# RelayBoard1_0.net
KiCad netlist of a schematic drawn in EAGLE
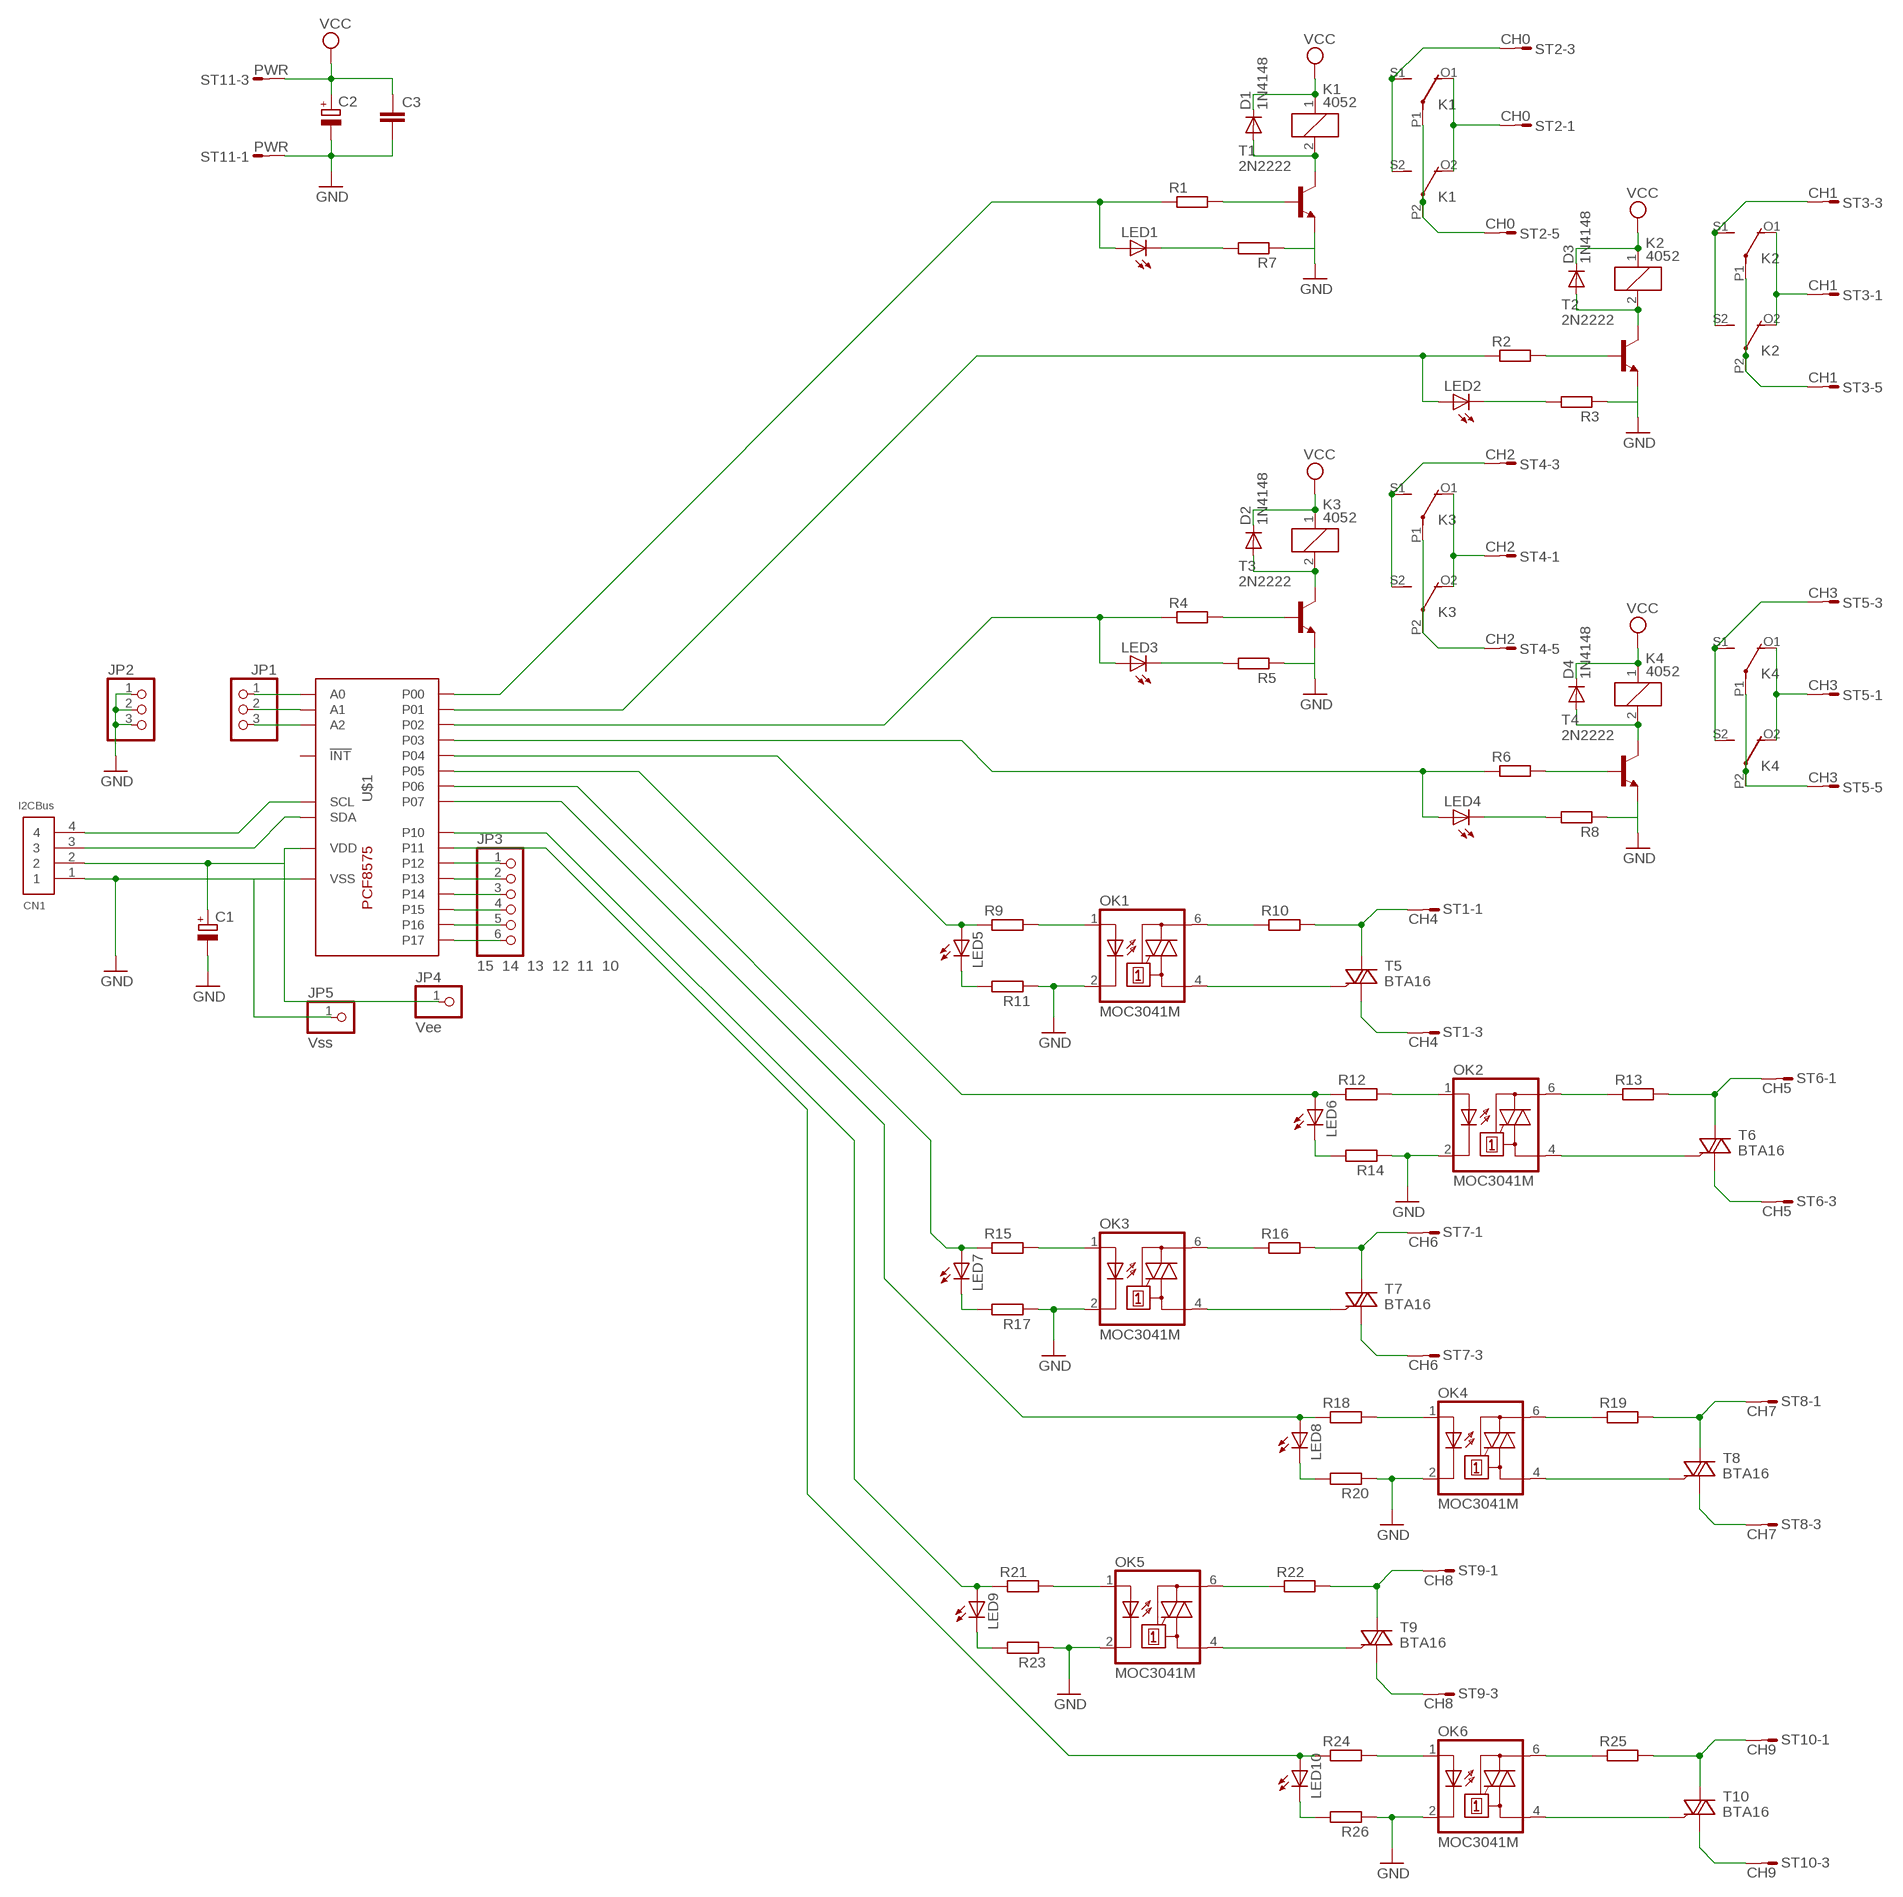
[diagram p0: schematic, sheet 1]

(export (version "E")
  (design (tool "Eeschema 10.0.6"))
  (components
    (comp (ref "C1")
      (value "CPOL-EUE3.5-8")
      (footprint "eagle-import:E3,5-8")
      (libsource (lib "eagle-import") (part "resistor_CPOL-EUE3.5-8"))
    )
    (comp (ref "C2")
      (value "CPOL-EUE2.5-7")
      (footprint "eagle-import:E2,5-7")
      (libsource (lib "eagle-import") (part "CPOL-EUE2.5-7"))
    )
    (comp (ref "C3")
      (value "C-EU050-025X075")
      (footprint "eagle-import:C050-025X075")
      (libsource (lib "eagle-import") (part "C-EU050-025X075"))
    )
    (comp (ref "CN1")
      (value "I2CBus")
      (footprint "eagle-import:1X04-BIG")
      (libsource (lib "eagle-import") (part "1X4-BIG"))
    )
    (comp (ref "D1")
      (value "1N4148")
      (footprint "eagle-import:DO35-7")
      (libsource (lib "eagle-import") (part "1N4148DO35-7"))
    )
    (comp (ref "D2")
      (value "1N4148")
      (footprint "eagle-import:DO35-7")
      (libsource (lib "eagle-import") (part "1N4148DO35-7"))
    )
    (comp (ref "D3")
      (value "1N4148")
      (footprint "eagle-import:DO35-7")
      (libsource (lib "eagle-import") (part "1N4148DO35-7"))
    )
    (comp (ref "D4")
      (value "1N4148")
      (footprint "eagle-import:DO35-7")
      (libsource (lib "eagle-import") (part "1N4148DO35-7"))
    )
    (comp (ref "JP1")
      (value "PINHD-1X3")
      (footprint "eagle-import:1X03")
      (libsource (lib "eagle-import") (part "PINHD-1X3"))
    )
    (comp (ref "JP2")
      (value "PINHD-1X3")
      (footprint "eagle-import:1X03")
      (libsource (lib "eagle-import") (part "PINHD-1X3"))
    )
    (comp (ref "JP3")
      (value "15 14 13 12 11 10")
      (footprint "eagle-import:1X06-CLEANBIG")
      (libsource (lib "eagle-import") (part "PINHD-1X6CB"))
    )
    (comp (ref "JP4")
      (value "Vee")
      (footprint "eagle-import:1X01-CLEANBIG")
      (libsource (lib "eagle-import") (part "PINHD-1X1CB"))
    )
    (comp (ref "JP5")
      (value "Vss")
      (footprint "eagle-import:1X01-CLEANBIG")
      (libsource (lib "eagle-import") (part "PINHD-1X1CB"))
    )
    (comp (ref "K1")
      (value "4052")
      (footprint "eagle-import:F4052")
      (libsource (lib "eagle-import") (part "4052"))
    )
    (comp (ref "K2")
      (value "4052")
      (footprint "eagle-import:F4052")
      (libsource (lib "eagle-import") (part "4052"))
    )
    (comp (ref "K3")
      (value "4052")
      (footprint "eagle-import:F4052")
      (libsource (lib "eagle-import") (part "4052"))
    )
    (comp (ref "K4")
      (value "4052")
      (footprint "eagle-import:F4052")
      (libsource (lib "eagle-import") (part "4052"))
    )
    (comp (ref "LED1")
      (value "LED3MM")
      (footprint "eagle-import:LED3MM")
      (libsource (lib "eagle-import") (part "LED3MM"))
    )
    (comp (ref "LED2")
      (value "LED3MM")
      (footprint "eagle-import:LED3MM")
      (libsource (lib "eagle-import") (part "LED3MM"))
    )
    (comp (ref "LED3")
      (value "LED3MM")
      (footprint "eagle-import:LED3MM")
      (libsource (lib "eagle-import") (part "LED3MM"))
    )
    (comp (ref "LED4")
      (value "LED3MM")
      (footprint "eagle-import:LED3MM")
      (libsource (lib "eagle-import") (part "LED3MM"))
    )
    (comp (ref "LED5")
      (value "LEDCHIPLED_0805")
      (footprint "eagle-import:CHIPLED_0805")
      (libsource (lib "eagle-import") (part "LEDCHIPLED_0805"))
    )
    (comp (ref "LED6")
      (value "LEDCHIPLED_0805")
      (footprint "eagle-import:CHIPLED_0805")
      (libsource (lib "eagle-import") (part "LEDCHIPLED_0805"))
    )
    (comp (ref "LED7")
      (value "LEDCHIPLED_0805")
      (footprint "eagle-import:CHIPLED_0805")
      (libsource (lib "eagle-import") (part "LEDCHIPLED_0805"))
    )
    (comp (ref "LED8")
      (value "LEDCHIPLED_0805")
      (footprint "eagle-import:CHIPLED_0805")
      (libsource (lib "eagle-import") (part "LEDCHIPLED_0805"))
    )
    (comp (ref "LED9")
      (value "LEDCHIPLED_0805")
      (footprint "eagle-import:CHIPLED_0805")
      (libsource (lib "eagle-import") (part "LEDCHIPLED_0805"))
    )
    (comp (ref "LED10")
      (value "LEDCHIPLED_0805")
      (footprint "eagle-import:CHIPLED_0805")
      (libsource (lib "eagle-import") (part "LEDCHIPLED_0805"))
    )
    (comp (ref "OK1")
      (value "MOC3041M")
      (footprint "eagle-import:DIL06")
      (fields (field (name "MF") "FAIRCHILD SEMICONDUCTOR"))
      (libsource (lib "eagle-import") (part "MOC3041M"))
    )
    (comp (ref "OK2")
      (value "MOC3041M")
      (footprint "eagle-import:DIL06")
      (fields (field (name "MF") "FAIRCHILD SEMICONDUCTOR"))
      (libsource (lib "eagle-import") (part "MOC3041M"))
    )
    (comp (ref "OK3")
      (value "MOC3041M")
      (footprint "eagle-import:DIL06")
      (fields (field (name "MF") "FAIRCHILD SEMICONDUCTOR"))
      (libsource (lib "eagle-import") (part "MOC3041M"))
    )
    (comp (ref "OK4")
      (value "MOC3041M")
      (footprint "eagle-import:DIL06")
      (fields (field (name "MF") "FAIRCHILD SEMICONDUCTOR"))
      (libsource (lib "eagle-import") (part "MOC3041M"))
    )
    (comp (ref "OK5")
      (value "MOC3041M")
      (footprint "eagle-import:DIL06")
      (fields (field (name "MF") "FAIRCHILD SEMICONDUCTOR"))
      (libsource (lib "eagle-import") (part "MOC3041M"))
    )
    (comp (ref "OK6")
      (value "MOC3041M")
      (footprint "eagle-import:DIL06")
      (fields (field (name "MF") "FAIRCHILD SEMICONDUCTOR"))
      (libsource (lib "eagle-import") (part "MOC3041M"))
    )
    (comp (ref "R1")
      (value "R-EU_0204/7")
      (footprint "eagle-import:0204_7")
      (libsource (lib "eagle-import") (part "R-EU_0204/7"))
    )
    (comp (ref "R2")
      (value "R-EU_0204/7")
      (footprint "eagle-import:0204_7")
      (libsource (lib "eagle-import") (part "R-EU_0204/7"))
    )
    (comp (ref "R3")
      (value "R-EU_0207/2V")
      (footprint "eagle-import:0207_2V")
      (libsource (lib "eagle-import") (part "R-EU_0207/2V"))
    )
    (comp (ref "R4")
      (value "R-EU_0204/7")
      (footprint "eagle-import:0204_7")
      (libsource (lib "eagle-import") (part "R-EU_0204/7"))
    )
    (comp (ref "R5")
      (value "R-EU_0207/2V")
      (footprint "eagle-import:0207_2V")
      (libsource (lib "eagle-import") (part "R-EU_0207/2V"))
    )
    (comp (ref "R6")
      (value "R-EU_0204/7")
      (footprint "eagle-import:0204_7")
      (libsource (lib "eagle-import") (part "R-EU_0204/7"))
    )
    (comp (ref "R7")
      (value "R-EU_0207/2V")
      (footprint "eagle-import:0207_2V")
      (libsource (lib "eagle-import") (part "R-EU_0207/2V"))
    )
    (comp (ref "R8")
      (value "R-EU_0207/2V")
      (footprint "eagle-import:0207_2V")
      (libsource (lib "eagle-import") (part "R-EU_0207/2V"))
    )
    (comp (ref "R9")
      (value "R-EU_0207/2V")
      (footprint "eagle-import:0207_2V")
      (libsource (lib "eagle-import") (part "R-EU_0207/2V"))
    )
    (comp (ref "R10")
      (value "R-EU_0207/7")
      (footprint "eagle-import:0207_7")
      (libsource (lib "eagle-import") (part "R-EU_0207/7"))
    )
    (comp (ref "R11")
      (value "R-EU_M0805")
      (footprint "eagle-import:M0805")
      (libsource (lib "eagle-import") (part "R-EU_M0805"))
    )
    (comp (ref "R12")
      (value "R-EU_0207/2V")
      (footprint "eagle-import:0207_2V")
      (libsource (lib "eagle-import") (part "R-EU_0207/2V"))
    )
    (comp (ref "R13")
      (value "R-EU_0207/7")
      (footprint "eagle-import:0207_7")
      (libsource (lib "eagle-import") (part "R-EU_0207/7"))
    )
    (comp (ref "R14")
      (value "R-EU_M0805")
      (footprint "eagle-import:M0805")
      (libsource (lib "eagle-import") (part "R-EU_M0805"))
    )
    (comp (ref "R15")
      (value "R-EU_0207/2V")
      (footprint "eagle-import:0207_2V")
      (libsource (lib "eagle-import") (part "R-EU_0207/2V"))
    )
    (comp (ref "R16")
      (value "R-EU_0207/7")
      (footprint "eagle-import:0207_7")
      (libsource (lib "eagle-import") (part "R-EU_0207/7"))
    )
    (comp (ref "R17")
      (value "R-EU_M0805")
      (footprint "eagle-import:M0805")
      (libsource (lib "eagle-import") (part "R-EU_M0805"))
    )
    (comp (ref "R18")
      (value "R-EU_0207/2V")
      (footprint "eagle-import:0207_2V")
      (libsource (lib "eagle-import") (part "R-EU_0207/2V"))
    )
    (comp (ref "R19")
      (value "R-EU_0207/7")
      (footprint "eagle-import:0207_7")
      (libsource (lib "eagle-import") (part "R-EU_0207/7"))
    )
    (comp (ref "R20")
      (value "R-EU_M0805")
      (footprint "eagle-import:M0805")
      (libsource (lib "eagle-import") (part "R-EU_M0805"))
    )
    (comp (ref "R21")
      (value "R-EU_0207/2V")
      (footprint "eagle-import:0207_2V")
      (libsource (lib "eagle-import") (part "R-EU_0207/2V"))
    )
    (comp (ref "R22")
      (value "R-EU_0207/7")
      (footprint "eagle-import:0207_7")
      (libsource (lib "eagle-import") (part "R-EU_0207/7"))
    )
    (comp (ref "R23")
      (value "R-EU_M0805")
      (footprint "eagle-import:M0805")
      (libsource (lib "eagle-import") (part "R-EU_M0805"))
    )
    (comp (ref "R24")
      (value "R-EU_0207/2V")
      (footprint "eagle-import:0207_2V")
      (libsource (lib "eagle-import") (part "R-EU_0207/2V"))
    )
    (comp (ref "R25")
      (value "R-EU_0207/7")
      (footprint "eagle-import:0207_7")
      (libsource (lib "eagle-import") (part "R-EU_0207/7"))
    )
    (comp (ref "R26")
      (value "R-EU_M0805")
      (footprint "eagle-import:M0805")
      (libsource (lib "eagle-import") (part "R-EU_M0805"))
    )
    (comp (ref "ST1")
      (value "CH4")
      (footprint "eagle-import:MSF3")
      (libsource (lib "eagle-import") (part "MSF3"))
    )
    (comp (ref "ST2")
      (value "CH0")
      (footprint "eagle-import:MSF5")
      (libsource (lib "eagle-import") (part "MSF5"))
    )
    (comp (ref "ST3")
      (value "CH1")
      (footprint "eagle-import:MSF5")
      (libsource (lib "eagle-import") (part "MSF5"))
    )
    (comp (ref "ST4")
      (value "CH2")
      (footprint "eagle-import:MSF5")
      (libsource (lib "eagle-import") (part "MSF5"))
    )
    (comp (ref "ST5")
      (value "CH3")
      (footprint "eagle-import:MSF5")
      (libsource (lib "eagle-import") (part "MSF5"))
    )
    (comp (ref "ST6")
      (value "CH5")
      (footprint "eagle-import:MSF3")
      (libsource (lib "eagle-import") (part "MSF3"))
    )
    (comp (ref "ST7")
      (value "CH6")
      (footprint "eagle-import:MSF3")
      (libsource (lib "eagle-import") (part "MSF3"))
    )
    (comp (ref "ST8")
      (value "CH7")
      (footprint "eagle-import:MSF3")
      (libsource (lib "eagle-import") (part "MSF3"))
    )
    (comp (ref "ST9")
      (value "CH8")
      (footprint "eagle-import:MSF3")
      (libsource (lib "eagle-import") (part "MSF3"))
    )
    (comp (ref "ST10")
      (value "CH9")
      (footprint "eagle-import:MSF3")
      (libsource (lib "eagle-import") (part "MSF3"))
    )
    (comp (ref "ST11")
      (value "PWR")
      (footprint "eagle-import:MSF3")
      (libsource (lib "eagle-import") (part "MSF3"))
    )
    (comp (ref "T1")
      (value "2N2222")
      (footprint "eagle-import:TO92-EBC-OVAL")
      (libsource (lib "eagle-import") (part "2N2222"))
    )
    (comp (ref "T2")
      (value "2N2222")
      (footprint "eagle-import:TO92-EBC-OVAL")
      (libsource (lib "eagle-import") (part "2N2222"))
    )
    (comp (ref "T3")
      (value "2N2222")
      (footprint "eagle-import:TO92-EBC-OVAL")
      (libsource (lib "eagle-import") (part "2N2222"))
    )
    (comp (ref "T4")
      (value "2N2222")
      (footprint "eagle-import:TO92-EBC-OVAL")
      (libsource (lib "eagle-import") (part "2N2222"))
    )
    (comp (ref "T5")
      (value "BTA16")
      (footprint "eagle-import:TO220BV")
      (libsource (lib "eagle-import") (part "BT138-V"))
    )
    (comp (ref "T6")
      (value "BTA16")
      (footprint "eagle-import:TO220BV")
      (libsource (lib "eagle-import") (part "BT138-V"))
    )
    (comp (ref "T7")
      (value "BTA16")
      (footprint "eagle-import:TO220BV")
      (libsource (lib "eagle-import") (part "BT138-V"))
    )
    (comp (ref "T8")
      (value "BTA16")
      (footprint "eagle-import:TO220BV")
      (libsource (lib "eagle-import") (part "BT138-V"))
    )
    (comp (ref "T9")
      (value "BTA16")
      (footprint "eagle-import:TO220BV")
      (libsource (lib "eagle-import") (part "BT138-V"))
    )
    (comp (ref "T10")
      (value "BTA16")
      (footprint "eagle-import:TO220BV")
      (libsource (lib "eagle-import") (part "BT138-V"))
    )
    (comp (ref "U$1")
      (value "PCF8575C")
      (footprint "eagle-import:SOP24")
      (libsource (lib "eagle-import") (part "PCF8575C"))
    )
  )
  (nets
    (net (code "1") (name "GND") (class "Default")
      (node (ref "C1") (pin "-") (pinfunction "-_-") (pintype "passive"))
      (node (ref "C2") (pin "-") (pinfunction "-_-") (pintype "passive"))
      (node (ref "C3") (pin "2") (pinfunction "2_2") (pintype "passive"))
      (node (ref "CN1") (pin "1") (pinfunction "1_1") (pintype "bidirectional"))
      (node (ref "JP2") (pin "1") (pinfunction "1_1") (pintype "passive"))
      (node (ref "JP2") (pin "2") (pinfunction "2_2") (pintype "passive"))
      (node (ref "JP2") (pin "3") (pinfunction "3_3") (pintype "passive"))
      (node (ref "JP5") (pin "1") (pinfunction "1_1") (pintype "passive"))
      (node (ref "OK1") (pin "2") (pinfunction "C_2") (pintype "passive"))
      (node (ref "OK2") (pin "2") (pinfunction "C_2") (pintype "passive"))
      (node (ref "OK3") (pin "2") (pinfunction "C_2") (pintype "passive"))
      (node (ref "OK4") (pin "2") (pinfunction "C_2") (pintype "passive"))
      (node (ref "OK5") (pin "2") (pinfunction "C_2") (pintype "passive"))
      (node (ref "OK6") (pin "2") (pinfunction "C_2") (pintype "passive"))
      (node (ref "R11") (pin "1") (pinfunction "1_1") (pintype "passive"))
      (node (ref "R14") (pin "1") (pinfunction "1_1") (pintype "passive"))
      (node (ref "R17") (pin "1") (pinfunction "1_1") (pintype "passive"))
      (node (ref "R20") (pin "1") (pinfunction "1_1") (pintype "passive"))
      (node (ref "R23") (pin "1") (pinfunction "1_1") (pintype "passive"))
      (node (ref "R26") (pin "1") (pinfunction "1_1") (pintype "passive"))
      (node (ref "R3") (pin "1") (pinfunction "1_1") (pintype "passive"))
      (node (ref "R5") (pin "1") (pinfunction "1_1") (pintype "passive"))
      (node (ref "R7") (pin "1") (pinfunction "1_1") (pintype "passive"))
      (node (ref "R8") (pin "1") (pinfunction "1_1") (pintype "passive"))
      (node (ref "ST11") (pin "1") (pinfunction "S_1") (pintype "passive"))
      (node (ref "T1") (pin "E") (pinfunction "E_E") (pintype "passive"))
      (node (ref "T2") (pin "E") (pinfunction "E_E") (pintype "passive"))
      (node (ref "T3") (pin "E") (pinfunction "E_E") (pintype "passive"))
      (node (ref "T4") (pin "E") (pinfunction "E_E") (pintype "passive"))
      (node (ref "U$1") (pin "P$12") (pinfunction "VSS_P$12") (pintype "power_in"))
    )
    (net (code "2") (name "Net-(D1-PadA)") (class "Default")
      (node (ref "D1") (pin "A") (pinfunction "A_A") (pintype "passive"))
      (node (ref "K1") (pin "2") (pinfunction "2_2") (pintype "passive"))
      (node (ref "T1") (pin "C") (pinfunction "C_C") (pintype "passive"))
    )
    (net (code "3") (name "Net-(D2-PadA)") (class "Default")
      (node (ref "D2") (pin "A") (pinfunction "A_A") (pintype "passive"))
      (node (ref "K3") (pin "2") (pinfunction "2_2") (pintype "passive"))
      (node (ref "T3") (pin "C") (pinfunction "C_C") (pintype "passive"))
    )
    (net (code "4") (name "Net-(D3-PadA)") (class "Default")
      (node (ref "D3") (pin "A") (pinfunction "A_A") (pintype "passive"))
      (node (ref "K2") (pin "2") (pinfunction "2_2") (pintype "passive"))
      (node (ref "T2") (pin "C") (pinfunction "C_C") (pintype "passive"))
    )
    (net (code "5") (name "Net-(D4-PadA)") (class "Default")
      (node (ref "D4") (pin "A") (pinfunction "A_A") (pintype "passive"))
      (node (ref "K4") (pin "2") (pinfunction "2_2") (pintype "passive"))
      (node (ref "T4") (pin "C") (pinfunction "C_C") (pintype "passive"))
    )
    (net (code "6") (name "Net-(K1B-O)") (class "Default")
      (node (ref "K1") (pin "O1") (pinfunction "O_O1") (pintype "passive"))
      (node (ref "K1") (pin "O2") (pinfunction "O_O2") (pintype "passive"))
      (node (ref "ST2") (pin "1") (pinfunction "S_1") (pintype "passive"))
    )
    (net (code "7") (name "Net-(K1B-P)") (class "Default")
      (node (ref "K1") (pin "P1") (pinfunction "P_P1") (pintype "passive"))
      (node (ref "K1") (pin "P2") (pinfunction "P_P2") (pintype "passive"))
      (node (ref "ST2") (pin "5") (pinfunction "S_5") (pintype "passive"))
    )
    (net (code "8") (name "Net-(K1B-S)") (class "Default")
      (node (ref "K1") (pin "S1") (pinfunction "S_S1") (pintype "passive"))
      (node (ref "K1") (pin "S2") (pinfunction "S_S2") (pintype "passive"))
      (node (ref "ST2") (pin "3") (pinfunction "S_3") (pintype "passive"))
    )
    (net (code "9") (name "Net-(K2B-O)") (class "Default")
      (node (ref "K2") (pin "O1") (pinfunction "O_O1") (pintype "passive"))
      (node (ref "K2") (pin "O2") (pinfunction "O_O2") (pintype "passive"))
      (node (ref "ST3") (pin "1") (pinfunction "S_1") (pintype "passive"))
    )
    (net (code "10") (name "Net-(K2B-P)") (class "Default")
      (node (ref "K2") (pin "P1") (pinfunction "P_P1") (pintype "passive"))
      (node (ref "K2") (pin "P2") (pinfunction "P_P2") (pintype "passive"))
      (node (ref "ST3") (pin "5") (pinfunction "S_5") (pintype "passive"))
    )
    (net (code "11") (name "Net-(K2B-S)") (class "Default")
      (node (ref "K2") (pin "S1") (pinfunction "S_S1") (pintype "passive"))
      (node (ref "K2") (pin "S2") (pinfunction "S_S2") (pintype "passive"))
      (node (ref "ST3") (pin "3") (pinfunction "S_3") (pintype "passive"))
    )
    (net (code "12") (name "Net-(K3B-O)") (class "Default")
      (node (ref "K3") (pin "O1") (pinfunction "O_O1") (pintype "passive"))
      (node (ref "K3") (pin "O2") (pinfunction "O_O2") (pintype "passive"))
      (node (ref "ST4") (pin "1") (pinfunction "S_1") (pintype "passive"))
    )
    (net (code "13") (name "Net-(K3B-P)") (class "Default")
      (node (ref "K3") (pin "P1") (pinfunction "P_P1") (pintype "passive"))
      (node (ref "K3") (pin "P2") (pinfunction "P_P2") (pintype "passive"))
      (node (ref "ST4") (pin "5") (pinfunction "S_5") (pintype "passive"))
    )
    (net (code "14") (name "Net-(K3B-S)") (class "Default")
      (node (ref "K3") (pin "S1") (pinfunction "S_S1") (pintype "passive"))
      (node (ref "K3") (pin "S2") (pinfunction "S_S2") (pintype "passive"))
      (node (ref "ST4") (pin "3") (pinfunction "S_3") (pintype "passive"))
    )
    (net (code "15") (name "Net-(K4B-O)") (class "Default")
      (node (ref "K4") (pin "O1") (pinfunction "O_O1") (pintype "passive"))
      (node (ref "K4") (pin "O2") (pinfunction "O_O2") (pintype "passive"))
      (node (ref "ST5") (pin "1") (pinfunction "S_1") (pintype "passive"))
    )
    (net (code "16") (name "Net-(K4B-P)") (class "Default")
      (node (ref "K4") (pin "P1") (pinfunction "P_P1") (pintype "passive"))
      (node (ref "K4") (pin "P2") (pinfunction "P_P2") (pintype "passive"))
      (node (ref "ST5") (pin "5") (pinfunction "S_5") (pintype "passive"))
    )
    (net (code "17") (name "Net-(K4B-S)") (class "Default")
      (node (ref "K4") (pin "S1") (pinfunction "S_S1") (pintype "passive"))
      (node (ref "K4") (pin "S2") (pinfunction "S_S2") (pintype "passive"))
      (node (ref "ST5") (pin "3") (pinfunction "S_3") (pintype "passive"))
    )
    (net (code "18") (name "Net-(LED1-C)") (class "Default")
      (node (ref "LED1") (pin "K") (pinfunction "C_K") (pintype "passive"))
      (node (ref "R7") (pin "2") (pinfunction "2_2") (pintype "passive"))
    )
    (net (code "19") (name "Net-(LED2-C)") (class "Default")
      (node (ref "LED2") (pin "K") (pinfunction "C_K") (pintype "passive"))
      (node (ref "R3") (pin "2") (pinfunction "2_2") (pintype "passive"))
    )
    (net (code "20") (name "Net-(LED3-C)") (class "Default")
      (node (ref "LED3") (pin "K") (pinfunction "C_K") (pintype "passive"))
      (node (ref "R5") (pin "2") (pinfunction "2_2") (pintype "passive"))
    )
    (net (code "21") (name "Net-(LED4-C)") (class "Default")
      (node (ref "LED4") (pin "K") (pinfunction "C_K") (pintype "passive"))
      (node (ref "R8") (pin "2") (pinfunction "2_2") (pintype "passive"))
    )
    (net (code "22") (name "Net-(LED5-PadC)") (class "Default")
      (node (ref "LED5") (pin "C") (pinfunction "C_C") (pintype "passive"))
      (node (ref "R11") (pin "2") (pinfunction "2_2") (pintype "passive"))
    )
    (net (code "23") (name "Net-(LED6-PadC)") (class "Default")
      (node (ref "LED6") (pin "C") (pinfunction "C_C") (pintype "passive"))
      (node (ref "R14") (pin "2") (pinfunction "2_2") (pintype "passive"))
    )
    (net (code "24") (name "Net-(LED7-PadC)") (class "Default")
      (node (ref "LED7") (pin "C") (pinfunction "C_C") (pintype "passive"))
      (node (ref "R17") (pin "2") (pinfunction "2_2") (pintype "passive"))
    )
    (net (code "25") (name "Net-(LED8-PadC)") (class "Default")
      (node (ref "LED8") (pin "C") (pinfunction "C_C") (pintype "passive"))
      (node (ref "R20") (pin "2") (pinfunction "2_2") (pintype "passive"))
    )
    (net (code "26") (name "Net-(LED9-PadC)") (class "Default")
      (node (ref "LED9") (pin "C") (pinfunction "C_C") (pintype "passive"))
      (node (ref "R23") (pin "2") (pinfunction "2_2") (pintype "passive"))
    )
    (net (code "27") (name "Net-(LED10-PadC)") (class "Default")
      (node (ref "LED10") (pin "C") (pinfunction "C_C") (pintype "passive"))
      (node (ref "R26") (pin "2") (pinfunction "2_2") (pintype "passive"))
    )
    (net (code "28") (name "Net-(OK1-A)") (class "Default")
      (node (ref "OK1") (pin "1") (pinfunction "A_1") (pintype "passive"))
      (node (ref "R9") (pin "2") (pinfunction "2_2") (pintype "passive"))
    )
    (net (code "29") (name "Net-(OK1-A1)") (class "Default")
      (node (ref "OK1") (pin "4") (pinfunction "A1_4") (pintype "passive"))
      (node (ref "T5") (pin "G") (pinfunction "G_G") (pintype "passive"))
    )
    (net (code "30") (name "Net-(OK1-A2)") (class "Default")
      (node (ref "OK1") (pin "6") (pinfunction "A2_6") (pintype "passive"))
      (node (ref "R10") (pin "1") (pinfunction "1_1") (pintype "passive"))
    )
    (net (code "31") (name "Net-(OK2-A)") (class "Default")
      (node (ref "OK2") (pin "1") (pinfunction "A_1") (pintype "passive"))
      (node (ref "R12") (pin "2") (pinfunction "2_2") (pintype "passive"))
    )
    (net (code "32") (name "Net-(OK2-A1)") (class "Default")
      (node (ref "OK2") (pin "4") (pinfunction "A1_4") (pintype "passive"))
      (node (ref "T6") (pin "G") (pinfunction "G_G") (pintype "passive"))
    )
    (net (code "33") (name "Net-(OK2-A2)") (class "Default")
      (node (ref "OK2") (pin "6") (pinfunction "A2_6") (pintype "passive"))
      (node (ref "R13") (pin "1") (pinfunction "1_1") (pintype "passive"))
    )
    (net (code "34") (name "Net-(OK3-A)") (class "Default")
      (node (ref "OK3") (pin "1") (pinfunction "A_1") (pintype "passive"))
      (node (ref "R15") (pin "2") (pinfunction "2_2") (pintype "passive"))
    )
    (net (code "35") (name "Net-(OK3-A1)") (class "Default")
      (node (ref "OK3") (pin "4") (pinfunction "A1_4") (pintype "passive"))
      (node (ref "T7") (pin "G") (pinfunction "G_G") (pintype "passive"))
    )
    (net (code "36") (name "Net-(OK3-A2)") (class "Default")
      (node (ref "OK3") (pin "6") (pinfunction "A2_6") (pintype "passive"))
      (node (ref "R16") (pin "1") (pinfunction "1_1") (pintype "passive"))
    )
    (net (code "37") (name "Net-(OK4-A)") (class "Default")
      (node (ref "OK4") (pin "1") (pinfunction "A_1") (pintype "passive"))
      (node (ref "R18") (pin "2") (pinfunction "2_2") (pintype "passive"))
    )
    (net (code "38") (name "Net-(OK4-A1)") (class "Default")
      (node (ref "OK4") (pin "4") (pinfunction "A1_4") (pintype "passive"))
      (node (ref "T8") (pin "G") (pinfunction "G_G") (pintype "passive"))
    )
    (net (code "39") (name "Net-(OK4-A2)") (class "Default")
      (node (ref "OK4") (pin "6") (pinfunction "A2_6") (pintype "passive"))
      (node (ref "R19") (pin "1") (pinfunction "1_1") (pintype "passive"))
    )
    (net (code "40") (name "Net-(OK5-A)") (class "Default")
      (node (ref "OK5") (pin "1") (pinfunction "A_1") (pintype "passive"))
      (node (ref "R21") (pin "2") (pinfunction "2_2") (pintype "passive"))
    )
    (net (code "41") (name "Net-(OK5-A1)") (class "Default")
      (node (ref "OK5") (pin "4") (pinfunction "A1_4") (pintype "passive"))
      (node (ref "T9") (pin "G") (pinfunction "G_G") (pintype "passive"))
    )
    (net (code "42") (name "Net-(OK5-A2)") (class "Default")
      (node (ref "OK5") (pin "6") (pinfunction "A2_6") (pintype "passive"))
      (node (ref "R22") (pin "1") (pinfunction "1_1") (pintype "passive"))
    )
    (net (code "43") (name "Net-(OK6-A)") (class "Default")
      (node (ref "OK6") (pin "1") (pinfunction "A_1") (pintype "passive"))
      (node (ref "R24") (pin "2") (pinfunction "2_2") (pintype "passive"))
    )
    (net (code "44") (name "Net-(OK6-A1)") (class "Default")
      (node (ref "OK6") (pin "4") (pinfunction "A1_4") (pintype "passive"))
      (node (ref "T10") (pin "G") (pinfunction "G_G") (pintype "passive"))
    )
    (net (code "45") (name "Net-(OK6-A2)") (class "Default")
      (node (ref "OK6") (pin "6") (pinfunction "A2_6") (pintype "passive"))
      (node (ref "R25") (pin "1") (pinfunction "1_1") (pintype "passive"))
    )
    (net (code "46") (name "Net-(R1-Pad2)") (class "Default")
      (node (ref "R1") (pin "2") (pinfunction "2_2") (pintype "passive"))
      (node (ref "T1") (pin "B") (pinfunction "B_B") (pintype "passive"))
    )
    (net (code "47") (name "Net-(R2-Pad2)") (class "Default")
      (node (ref "R2") (pin "2") (pinfunction "2_2") (pintype "passive"))
      (node (ref "T2") (pin "B") (pinfunction "B_B") (pintype "passive"))
    )
    (net (code "48") (name "Net-(R4-Pad2)") (class "Default")
      (node (ref "R4") (pin "2") (pinfunction "2_2") (pintype "passive"))
      (node (ref "T3") (pin "B") (pinfunction "B_B") (pintype "passive"))
    )
    (net (code "49") (name "Net-(R6-Pad2)") (class "Default")
      (node (ref "R6") (pin "2") (pinfunction "2_2") (pintype "passive"))
      (node (ref "T4") (pin "B") (pinfunction "B_B") (pintype "passive"))
    )
    (net (code "50") (name "Net-(ST1A-S)") (class "Default")
      (node (ref "R10") (pin "2") (pinfunction "2_2") (pintype "passive"))
      (node (ref "ST1") (pin "1") (pinfunction "S_1") (pintype "passive"))
      (node (ref "T5") (pin "T2") (pinfunction "A2_T2") (pintype "passive"))
    )
    (net (code "51") (name "Net-(ST1C-S)") (class "Default")
      (node (ref "ST1") (pin "3") (pinfunction "S_3") (pintype "passive"))
      (node (ref "T5") (pin "T1") (pinfunction "A1_T1") (pintype "passive"))
    )
    (net (code "52") (name "Net-(ST6A-S)") (class "Default")
      (node (ref "R13") (pin "2") (pinfunction "2_2") (pintype "passive"))
      (node (ref "ST6") (pin "1") (pinfunction "S_1") (pintype "passive"))
      (node (ref "T6") (pin "T2") (pinfunction "A2_T2") (pintype "passive"))
    )
    (net (code "53") (name "Net-(ST6C-S)") (class "Default")
      (node (ref "ST6") (pin "3") (pinfunction "S_3") (pintype "passive"))
      (node (ref "T6") (pin "T1") (pinfunction "A1_T1") (pintype "passive"))
    )
    (net (code "54") (name "Net-(ST7A-S)") (class "Default")
      (node (ref "R16") (pin "2") (pinfunction "2_2") (pintype "passive"))
      (node (ref "ST7") (pin "1") (pinfunction "S_1") (pintype "passive"))
      (node (ref "T7") (pin "T2") (pinfunction "A2_T2") (pintype "passive"))
    )
    (net (code "55") (name "Net-(ST7C-S)") (class "Default")
      (node (ref "ST7") (pin "3") (pinfunction "S_3") (pintype "passive"))
      (node (ref "T7") (pin "T1") (pinfunction "A1_T1") (pintype "passive"))
    )
    (net (code "56") (name "Net-(ST8A-S)") (class "Default")
      (node (ref "R19") (pin "2") (pinfunction "2_2") (pintype "passive"))
      (node (ref "ST8") (pin "1") (pinfunction "S_1") (pintype "passive"))
      (node (ref "T8") (pin "T2") (pinfunction "A2_T2") (pintype "passive"))
    )
    (net (code "57") (name "Net-(ST8C-S)") (class "Default")
      (node (ref "ST8") (pin "3") (pinfunction "S_3") (pintype "passive"))
      (node (ref "T8") (pin "T1") (pinfunction "A1_T1") (pintype "passive"))
    )
    (net (code "58") (name "Net-(ST9A-S)") (class "Default")
      (node (ref "R22") (pin "2") (pinfunction "2_2") (pintype "passive"))
      (node (ref "ST9") (pin "1") (pinfunction "S_1") (pintype "passive"))
      (node (ref "T9") (pin "T2") (pinfunction "A2_T2") (pintype "passive"))
    )
    (net (code "59") (name "Net-(ST9C-S)") (class "Default")
      (node (ref "ST9") (pin "3") (pinfunction "S_3") (pintype "passive"))
      (node (ref "T9") (pin "T1") (pinfunction "A1_T1") (pintype "passive"))
    )
    (net (code "60") (name "Net-(ST10A-S)") (class "Default")
      (node (ref "R25") (pin "2") (pinfunction "2_2") (pintype "passive"))
      (node (ref "ST10") (pin "1") (pinfunction "S_1") (pintype "passive"))
      (node (ref "T10") (pin "T2") (pinfunction "A2_T2") (pintype "passive"))
    )
    (net (code "61") (name "Net-(ST10C-S)") (class "Default")
      (node (ref "ST10") (pin "3") (pinfunction "S_3") (pintype "passive"))
      (node (ref "T10") (pin "T1") (pinfunction "A1_T1") (pintype "passive"))
    )
    (net (code "62") (name "Net-(U$1-A0)") (class "Default")
      (node (ref "JP1") (pin "1") (pinfunction "1_1") (pintype "passive"))
      (node (ref "U$1") (pin "P$21") (pinfunction "A0_P$21") (pintype "input"))
    )
    (net (code "63") (name "Net-(U$1-A1)") (class "Default")
      (node (ref "JP1") (pin "2") (pinfunction "2_2") (pintype "passive"))
      (node (ref "U$1") (pin "P$2") (pinfunction "A1_P$2") (pintype "input"))
    )
    (net (code "64") (name "Net-(U$1-A2)") (class "Default")
      (node (ref "JP1") (pin "3") (pinfunction "3_3") (pintype "passive"))
      (node (ref "U$1") (pin "P$3") (pinfunction "A2_P$3") (pintype "input"))
    )
    (net (code "65") (name "Net-(U$1-P00)") (class "Default")
      (node (ref "LED1") (pin "A") (pinfunction "A_A") (pintype "passive"))
      (node (ref "R1") (pin "1") (pinfunction "1_1") (pintype "passive"))
      (node (ref "U$1") (pin "P$4") (pinfunction "P00_P$4") (pintype "bidirectional"))
    )
    (net (code "66") (name "Net-(U$1-P01)") (class "Default")
      (node (ref "LED2") (pin "A") (pinfunction "A_A") (pintype "passive"))
      (node (ref "R2") (pin "1") (pinfunction "1_1") (pintype "passive"))
      (node (ref "U$1") (pin "P$5") (pinfunction "P01_P$5") (pintype "bidirectional"))
    )
    (net (code "67") (name "Net-(U$1-P02)") (class "Default")
      (node (ref "LED3") (pin "A") (pinfunction "A_A") (pintype "passive"))
      (node (ref "R4") (pin "1") (pinfunction "1_1") (pintype "passive"))
      (node (ref "U$1") (pin "P$6") (pinfunction "P02_P$6") (pintype "bidirectional"))
    )
    (net (code "68") (name "Net-(U$1-P03)") (class "Default")
      (node (ref "LED4") (pin "A") (pinfunction "A_A") (pintype "passive"))
      (node (ref "R6") (pin "1") (pinfunction "1_1") (pintype "passive"))
      (node (ref "U$1") (pin "P$7") (pinfunction "P03_P$7") (pintype "bidirectional"))
    )
    (net (code "69") (name "Net-(U$1-P04)") (class "Default")
      (node (ref "LED5") (pin "A") (pinfunction "A_A") (pintype "passive"))
      (node (ref "R9") (pin "1") (pinfunction "1_1") (pintype "passive"))
      (node (ref "U$1") (pin "P$8") (pinfunction "P04_P$8") (pintype "bidirectional"))
    )
    (net (code "70") (name "Net-(U$1-P05)") (class "Default")
      (node (ref "LED6") (pin "A") (pinfunction "A_A") (pintype "passive"))
      (node (ref "R12") (pin "1") (pinfunction "1_1") (pintype "passive"))
      (node (ref "U$1") (pin "P$9") (pinfunction "P05_P$9") (pintype "bidirectional"))
    )
    (net (code "71") (name "Net-(U$1-P06)") (class "Default")
      (node (ref "LED7") (pin "A") (pinfunction "A_A") (pintype "passive"))
      (node (ref "R15") (pin "1") (pinfunction "1_1") (pintype "passive"))
      (node (ref "U$1") (pin "P$10") (pinfunction "P06_P$10") (pintype "bidirectional"))
    )
    (net (code "72") (name "Net-(U$1-P07)") (class "Default")
      (node (ref "LED8") (pin "A") (pinfunction "A_A") (pintype "passive"))
      (node (ref "R18") (pin "1") (pinfunction "1_1") (pintype "passive"))
      (node (ref "U$1") (pin "P$11") (pinfunction "P07_P$11") (pintype "bidirectional"))
    )
    (net (code "73") (name "Net-(U$1-P10)") (class "Default")
      (node (ref "LED9") (pin "A") (pinfunction "A_A") (pintype "passive"))
      (node (ref "R21") (pin "1") (pinfunction "1_1") (pintype "passive"))
      (node (ref "U$1") (pin "P$13") (pinfunction "P10_P$13") (pintype "bidirectional"))
    )
    (net (code "74") (name "Net-(U$1-P11)") (class "Default")
      (node (ref "LED10") (pin "A") (pinfunction "A_A") (pintype "passive"))
      (node (ref "R24") (pin "1") (pinfunction "1_1") (pintype "passive"))
      (node (ref "U$1") (pin "P$14") (pinfunction "P11_P$14") (pintype "bidirectional"))
    )
    (net (code "75") (name "Net-(U$1-P12)") (class "Default")
      (node (ref "JP3") (pin "1") (pinfunction "1_1") (pintype "passive"))
      (node (ref "U$1") (pin "P$15") (pinfunction "P12_P$15") (pintype "bidirectional"))
    )
    (net (code "76") (name "Net-(U$1-P13)") (class "Default")
      (node (ref "JP3") (pin "2") (pinfunction "2_2") (pintype "passive"))
      (node (ref "U$1") (pin "P$16") (pinfunction "P13_P$16") (pintype "bidirectional"))
    )
    (net (code "77") (name "Net-(U$1-P14)") (class "Default")
      (node (ref "JP3") (pin "3") (pinfunction "3_3") (pintype "passive"))
      (node (ref "U$1") (pin "P$17") (pinfunction "P14_P$17") (pintype "bidirectional"))
    )
    (net (code "78") (name "Net-(U$1-P15)") (class "Default")
      (node (ref "JP3") (pin "4") (pinfunction "4_4") (pintype "passive"))
      (node (ref "U$1") (pin "P$18") (pinfunction "P15_P$18") (pintype "bidirectional"))
    )
    (net (code "79") (name "Net-(U$1-P16)") (class "Default")
      (node (ref "JP3") (pin "5") (pinfunction "5_5") (pintype "passive"))
      (node (ref "U$1") (pin "P$19") (pinfunction "P16_P$19") (pintype "bidirectional"))
    )
    (net (code "80") (name "Net-(U$1-P17)") (class "Default")
      (node (ref "JP3") (pin "6") (pinfunction "6_6") (pintype "passive"))
      (node (ref "U$1") (pin "P$20") (pinfunction "P17_P$20") (pintype "bidirectional"))
    )
    (net (code "81") (name "Net-(U$1-SCL)") (class "Default")
      (node (ref "CN1") (pin "4") (pinfunction "4_4") (pintype "bidirectional"))
      (node (ref "U$1") (pin "P$22") (pinfunction "SCL_P$22") (pintype "input"))
    )
    (net (code "82") (name "Net-(U$1-SDA)") (class "Default")
      (node (ref "CN1") (pin "3") (pinfunction "3_3") (pintype "bidirectional"))
      (node (ref "U$1") (pin "P$23") (pinfunction "SDA_P$23") (pintype "bidirectional"))
    )
    (net (code "83") (name "Net-(U$1-VDD)") (class "Default")
      (node (ref "C1") (pin "+") (pinfunction "+_+") (pintype "passive"))
      (node (ref "CN1") (pin "2") (pinfunction "2_2") (pintype "bidirectional"))
      (node (ref "JP4") (pin "1") (pinfunction "1_1") (pintype "passive"))
      (node (ref "U$1") (pin "P$24") (pinfunction "VDD_P$24") (pintype "power_in"))
    )
    (net (code "84") (name "VCC") (class "Default")
      (node (ref "C2") (pin "+") (pinfunction "+_+") (pintype "passive"))
      (node (ref "C3") (pin "1") (pinfunction "1_1") (pintype "passive"))
      (node (ref "D1") (pin "C") (pinfunction "C_C") (pintype "passive"))
      (node (ref "D2") (pin "C") (pinfunction "C_C") (pintype "passive"))
      (node (ref "D3") (pin "C") (pinfunction "C_C") (pintype "passive"))
      (node (ref "D4") (pin "C") (pinfunction "C_C") (pintype "passive"))
      (node (ref "K1") (pin "1") (pinfunction "1_1") (pintype "passive"))
      (node (ref "K2") (pin "1") (pinfunction "1_1") (pintype "passive"))
      (node (ref "K3") (pin "1") (pinfunction "1_1") (pintype "passive"))
      (node (ref "K4") (pin "1") (pinfunction "1_1") (pintype "passive"))
      (node (ref "ST11") (pin "3") (pinfunction "S_3") (pintype "passive"))
    )
    (net (code "85") (name "unconnected-(U$1-~{INT}-PadP$1)") (class "Default")
      (node (ref "U$1") (pin "P$1") (pinfunction "~{INT}_P$1") (pintype "open_collector"))
    )
  )
)
